# RP2040.net
KiCad netlist of a schematic drawn in Altium Designer
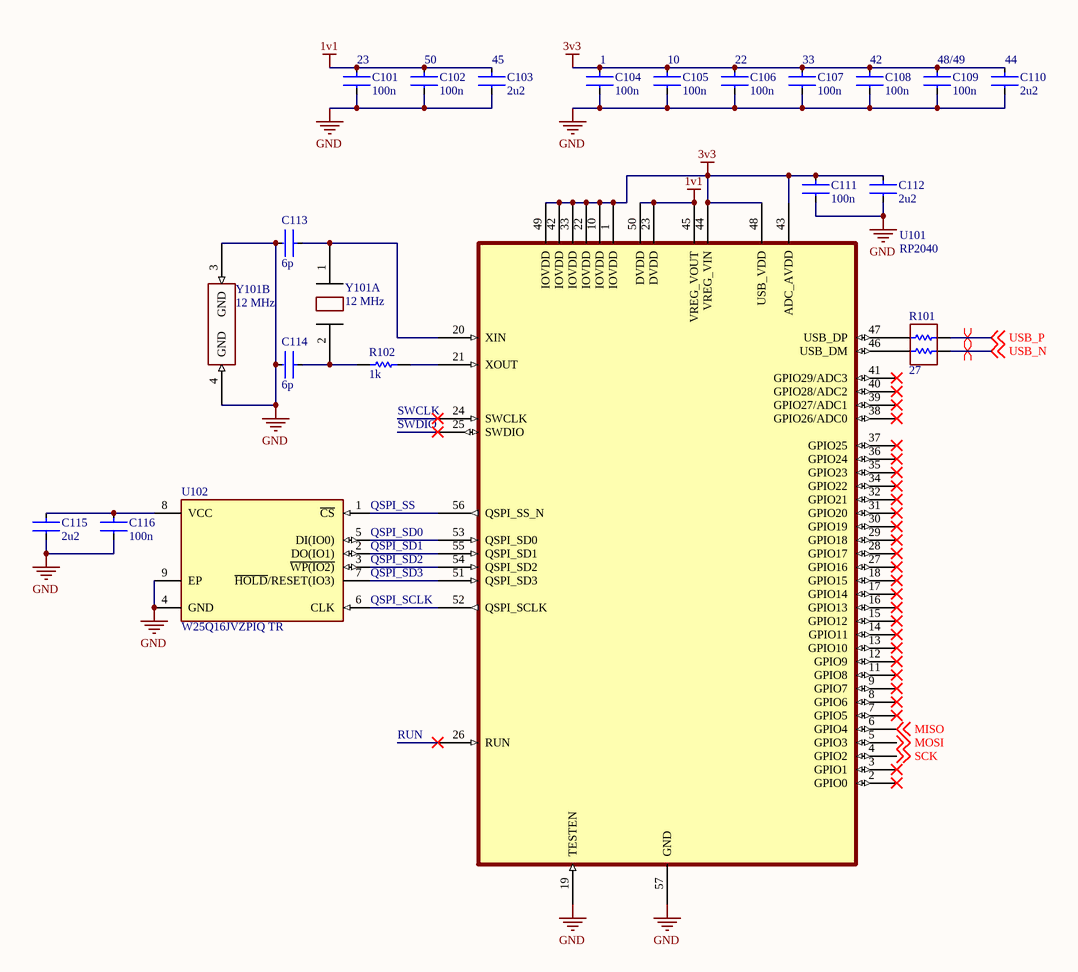
[diagram p0: RP2040.SchDoc]

(export (version "E")
  (design (tool "Eeschema 10.0.6"))
  (components
    (comp (ref "C101")
      (value "100n")
      (footprint "FP-GCM155-0_05-MFG")
      (description "Ceramic Capacitor for Automotive 100nF ±10% 50VDC X7R 0402 Paper T/R")
      (fields (field (name "TOLERANCE") "10%"))
      (libsource (lib "Main") (part "GCM155R71H104KE02J"))
    )
    (comp (ref "C102")
      (value "100n")
      (footprint "FP-GCM155-0_05-MFG")
      (description "Ceramic Capacitor for Automotive 100nF ±10% 50VDC X7R 0402 Paper T/R")
      (fields (field (name "TOLERANCE") "10%"))
      (libsource (lib "Main") (part "GCM155R71H104KE02J"))
    )
    (comp (ref "C103")
      (value "2u2")
      (footprint "CAPC1608X10N")
      (description "Multilayer Ceramic Capacitors MLCC - SMD/SMT 0603 50Vdc 2.2uF X5R 20%")
      (libsource (lib "Main") (part "GRT188R61H225ME13D"))
    )
    (comp (ref "C104")
      (value "100n")
      (footprint "FP-GCM155-0_05-MFG")
      (description "Ceramic Capacitor for Automotive 100nF ±10% 50VDC X7R 0402 Paper T/R")
      (fields (field (name "TOLERANCE") "10%"))
      (libsource (lib "Main") (part "GCM155R71H104KE02J"))
    )
    (comp (ref "C105")
      (value "100n")
      (footprint "FP-GCM155-0_05-MFG")
      (description "Ceramic Capacitor for Automotive 100nF ±10% 50VDC X7R 0402 Paper T/R")
      (fields (field (name "TOLERANCE") "10%"))
      (libsource (lib "Main") (part "GCM155R71H104KE02J"))
    )
    (comp (ref "C106")
      (value "100n")
      (footprint "FP-GCM155-0_05-MFG")
      (description "Ceramic Capacitor for Automotive 100nF ±10% 50VDC X7R 0402 Paper T/R")
      (fields (field (name "TOLERANCE") "10%"))
      (libsource (lib "Main") (part "GCM155R71H104KE02J"))
    )
    (comp (ref "C107")
      (value "100n")
      (footprint "FP-GCM155-0_05-MFG")
      (description "Ceramic Capacitor for Automotive 100nF ±10% 50VDC X7R 0402 Paper T/R")
      (fields (field (name "TOLERANCE") "10%"))
      (libsource (lib "Main") (part "GCM155R71H104KE02J"))
    )
    (comp (ref "C108")
      (value "100n")
      (footprint "FP-GCM155-0_05-MFG")
      (description "Ceramic Capacitor for Automotive 100nF ±10% 50VDC X7R 0402 Paper T/R")
      (fields (field (name "TOLERANCE") "10%"))
      (libsource (lib "Main") (part "GCM155R71H104KE02J"))
    )
    (comp (ref "C109")
      (value "100n")
      (footprint "FP-GCM155-0_05-MFG")
      (description "Ceramic Capacitor for Automotive 100nF ±10% 50VDC X7R 0402 Paper T/R")
      (fields (field (name "TOLERANCE") "10%"))
      (libsource (lib "Main") (part "GCM155R71H104KE02J"))
    )
    (comp (ref "C110")
      (value "2u2")
      (footprint "CAPC1608X10N")
      (description "Multilayer Ceramic Capacitors MLCC - SMD/SMT 0603 50Vdc 2.2uF X5R 20%")
      (libsource (lib "Main") (part "GRT188R61H225ME13D"))
    )
    (comp (ref "C111")
      (value "100n")
      (footprint "FP-GCM155-0_05-MFG")
      (description "Ceramic Capacitor for Automotive 100nF ±10% 50VDC X7R 0402 Paper T/R")
      (fields (field (name "TOLERANCE") "10%"))
      (libsource (lib "Main") (part "GCM155R71H104KE02J"))
    )
    (comp (ref "C112")
      (value "2u2")
      (footprint "CAPC1608X10N")
      (description "Multilayer Ceramic Capacitors MLCC - SMD/SMT 0603 50Vdc 2.2uF X5R 20%")
      (libsource (lib "Main") (part "GRT188R61H225ME13D"))
    )
    (comp (ref "C113")
      (value "6p")
      (footprint "FP-GCQ155-0_05-MFG")
      (description "High Q Ceramic Capacitor for Automotive 6pF ±0.1pF 50VDC C0G 0402 Paper T/R")
      (libsource (lib "Main") (part "GCQ1555C1H6R0BB01D"))
    )
    (comp (ref "C114")
      (value "6p")
      (footprint "FP-GCQ155-0_05-MFG")
      (description "High Q Ceramic Capacitor for Automotive 6pF ±0.1pF 50VDC C0G 0402 Paper T/R")
      (libsource (lib "Main") (part "GCQ1555C1H6R0BB01D"))
    )
    (comp (ref "C115")
      (value "2u2")
      (footprint "CAPC1608X10N")
      (description "Multilayer Ceramic Capacitors MLCC - SMD/SMT 0603 50Vdc 2.2uF X5R 20%")
      (libsource (lib "Main") (part "GRT188R61H225ME13D"))
    )
    (comp (ref "C116")
      (value "100n")
      (footprint "FP-GCM155-0_05-MFG")
      (description "Ceramic Capacitor for Automotive 100nF ±10% 50VDC X7R 0402 Paper T/R")
      (fields (field (name "TOLERANCE") "10%"))
      (libsource (lib "Main") (part "GCM155R71H104KE02J"))
    )
    (comp (ref "R101")
      (value "27")
      (footprint "CAC-65P100X100-4L")
      (libsource (lib "Main") (part "EXB-24V270JX"))
    )
    (comp (ref "R102")
      (value "1k")
      (footprint "RESC1005X04N")
      (fields (field (name "MANUFACTURER") "Panasonic") (field (name "PART NUMBER") "ERJ-2GEJ102X"))
      (libsource (lib "Main") (part "ERJ-2GEJ102X"))
    )
    (comp (ref "U101")
      (value "RP2040")
      (footprint "QFN40P700X700X90_HS-57N")
      (libsource (lib "Main") (part "RP2040"))
    )
    (comp (ref "U102")
      (value "W25Q16JVZPIQ TR")
      (footprint "WSON-8")
      (description "IC FLASH 16M SPI 133MHZ 8WSON")
      (libsource (lib "Main") (part "W25Q16JVZPIQ TR"))
    )
    (comp (ref "Y101") (value "12 MHz") (libsource (lib "Main") (part "ABM10-166-12.000MHZ-T3")))
  )
  (nets
    (net (code "1") (name "1v1") (class "Default")
      (node (ref "C101") (pin "1") (pinfunction "1_1") (pintype "passive"))
      (node (ref "C102") (pin "1") (pinfunction "1_1") (pintype "passive"))
      (node (ref "C103") (pin "1") (pinfunction "1_1") (pintype "passive"))
      (node (ref "U101") (pin "23") (pinfunction "DVDD_23") (pintype "power_in"))
      (node (ref "U101") (pin "45") (pinfunction "VREG_VOUT_45") (pintype "power_in"))
      (node (ref "U101") (pin "50") (pinfunction "DVDD_50") (pintype "power_in"))
    )
    (net (code "2") (name "3v3") (class "Default")
      (node (ref "C104") (pin "1") (pinfunction "1_1") (pintype "passive"))
      (node (ref "C105") (pin "1") (pinfunction "1_1") (pintype "passive"))
      (node (ref "C106") (pin "1") (pinfunction "1_1") (pintype "passive"))
      (node (ref "C107") (pin "1") (pinfunction "1_1") (pintype "passive"))
      (node (ref "C108") (pin "1") (pinfunction "1_1") (pintype "passive"))
      (node (ref "C109") (pin "1") (pinfunction "1_1") (pintype "passive"))
      (node (ref "C110") (pin "1") (pinfunction "1_1") (pintype "passive"))
      (node (ref "C111") (pin "1") (pinfunction "1_1") (pintype "passive"))
      (node (ref "C112") (pin "1") (pinfunction "1_1") (pintype "passive"))
      (node (ref "U101") (pin "1") (pinfunction "IOVDD_1") (pintype "power_in"))
      (node (ref "U101") (pin "10") (pinfunction "IOVDD_10") (pintype "power_in"))
      (node (ref "U101") (pin "22") (pinfunction "IOVDD_22") (pintype "power_in"))
      (node (ref "U101") (pin "33") (pinfunction "IOVDD_33") (pintype "power_in"))
      (node (ref "U101") (pin "42") (pinfunction "IOVDD_42") (pintype "power_in"))
      (node (ref "U101") (pin "43") (pinfunction "ADC_AVDD_43") (pintype "power_in"))
      (node (ref "U101") (pin "44") (pinfunction "VREG_VIN_44") (pintype "power_in"))
      (node (ref "U101") (pin "48") (pinfunction "USB_VDD_48") (pintype "power_in"))
      (node (ref "U101") (pin "49") (pinfunction "IOVDD_49") (pintype "power_in"))
    )
    (net (code "3") (name "GND") (class "Default")
      (node (ref "C101") (pin "2") (pinfunction "2_2") (pintype "passive"))
      (node (ref "C102") (pin "2") (pinfunction "2_2") (pintype "passive"))
      (node (ref "C103") (pin "2") (pinfunction "2_2") (pintype "passive"))
      (node (ref "C104") (pin "2") (pinfunction "2_2") (pintype "passive"))
      (node (ref "C105") (pin "2") (pinfunction "2_2") (pintype "passive"))
      (node (ref "C106") (pin "2") (pinfunction "2_2") (pintype "passive"))
      (node (ref "C107") (pin "2") (pinfunction "2_2") (pintype "passive"))
      (node (ref "C108") (pin "2") (pinfunction "2_2") (pintype "passive"))
      (node (ref "C109") (pin "2") (pinfunction "2_2") (pintype "passive"))
      (node (ref "C110") (pin "2") (pinfunction "2_2") (pintype "passive"))
      (node (ref "C111") (pin "2") (pinfunction "2_2") (pintype "passive"))
      (node (ref "C112") (pin "2") (pinfunction "2_2") (pintype "passive"))
      (node (ref "C113") (pin "2") (pinfunction "2_2") (pintype "passive"))
      (node (ref "C114") (pin "2") (pinfunction "2_2") (pintype "passive"))
      (node (ref "C115") (pin "2") (pinfunction "2_2") (pintype "passive"))
      (node (ref "C116") (pin "2") (pinfunction "2_2") (pintype "passive"))
      (node (ref "U101") (pin "19") (pinfunction "TESTEN_19") (pintype "input"))
      (node (ref "U101") (pin "57") (pinfunction "GND_57") (pintype "power_in"))
      (node (ref "U102") (pin "4") (pinfunction "GND_4") (pintype "power_in"))
      (node (ref "U102") (pin "9") (pinfunction "EP_9") (pintype "passive"))
      (node (ref "Y101") (pin "3") (pinfunction "GND_3") (pintype "input"))
      (node (ref "Y101") (pin "4") (pinfunction "GND_4") (pintype "input"))
    )
    (net (code "4") (name "MISO") (class "Default")
      (node (ref "U101") (pin "6") (pinfunction "GPIO4_6") (pintype "bidirectional"))
    )
    (net (code "5") (name "MOSI") (class "Default")
      (node (ref "U101") (pin "5") (pinfunction "GPIO3_5") (pintype "bidirectional"))
    )
    (net (code "6") (name "Net-(C114-Pad1)") (class "Default")
      (node (ref "C114") (pin "1") (pinfunction "1_1") (pintype "passive"))
      (node (ref "R102") (pin "1") (pinfunction "1_1") (pintype "passive"))
      (node (ref "Y101") (pin "2") (pintype "passive"))
    )
    (net (code "7") (name "Net-(U101-QSPI_SCLK)") (class "Default")
      (node (ref "U101") (pin "52") (pinfunction "QSPI_SCLK_52") (pintype "output"))
      (node (ref "U102") (pin "6") (pinfunction "CLK_6") (pintype "input"))
    )
    (net (code "8") (name "Net-(U101-QSPI_SD0)") (class "Default")
      (node (ref "U101") (pin "53") (pinfunction "QSPI_SD0_53") (pintype "input"))
      (node (ref "U102") (pin "5") (pinfunction "DI(IO0)_5") (pintype "bidirectional"))
    )
    (net (code "9") (name "Net-(U101-QSPI_SD1)") (class "Default")
      (node (ref "U101") (pin "55") (pinfunction "QSPI_SD1_55") (pintype "input"))
      (node (ref "U102") (pin "2") (pinfunction "DO(IO1)_2") (pintype "bidirectional"))
    )
    (net (code "10") (name "Net-(U101-QSPI_SD2)") (class "Default")
      (node (ref "U101") (pin "54") (pinfunction "QSPI_SD2_54") (pintype "input"))
      (node (ref "U102") (pin "3") (pinfunction "~{WP(IO2)}_3") (pintype "bidirectional"))
    )
    (net (code "11") (name "Net-(U101-QSPI_SD3)") (class "Default")
      (node (ref "U101") (pin "51") (pinfunction "QSPI_SD3_51") (pintype "input"))
      (node (ref "U102") (pin "7") (pinfunction "~{HOLD}/RESET(IO3)_7") (pintype "passive"))
    )
    (net (code "12") (name "Net-(U101-QSPI_SS_N)") (class "Default")
      (node (ref "U101") (pin "56") (pinfunction "QSPI_SS_N_56") (pintype "output"))
      (node (ref "U102") (pin "1") (pinfunction "~{CS}_1") (pintype "input"))
    )
    (net (code "13") (name "Net-(U101-USB_DM)") (class "Default")
      (node (ref "R101") (pin "2") (pinfunction "2_2") (pintype "passive"))
      (node (ref "U101") (pin "46") (pinfunction "USB_DM_46") (pintype "bidirectional"))
    )
    (net (code "14") (name "Net-(U101-USB_DP)") (class "Default")
      (node (ref "R101") (pin "1") (pinfunction "1_1") (pintype "passive"))
      (node (ref "U101") (pin "47") (pinfunction "USB_DP_47") (pintype "bidirectional"))
    )
    (net (code "15") (name "Net-(U101-XIN)") (class "Default")
      (node (ref "C113") (pin "1") (pinfunction "1_1") (pintype "passive"))
      (node (ref "U101") (pin "20") (pinfunction "XIN_20") (pintype "input"))
      (node (ref "Y101") (pin "1") (pintype "passive"))
    )
    (net (code "16") (name "Net-(U101-XOUT)") (class "Default")
      (node (ref "R102") (pin "2") (pinfunction "2_2") (pintype "passive"))
      (node (ref "U101") (pin "21") (pinfunction "XOUT_21") (pintype "input"))
    )
    (net (code "17") (name "Net-(U102-VCC)") (class "Default")
      (node (ref "C115") (pin "1") (pinfunction "1_1") (pintype "passive"))
      (node (ref "C116") (pin "1") (pinfunction "1_1") (pintype "passive"))
      (node (ref "U102") (pin "8") (pinfunction "VCC_8") (pintype "power_in"))
    )
    (net (code "18") (name "SCK") (class "Default")
      (node (ref "U101") (pin "4") (pinfunction "GPIO2_4") (pintype "bidirectional"))
    )
    (net (code "19") (name "USB_N") (class "Default")
      (node (ref "R101") (pin "3") (pinfunction "3_3") (pintype "passive"))
    )
    (net (code "20") (name "USB_P") (class "Default")
      (node (ref "R101") (pin "4") (pinfunction "4_4") (pintype "passive"))
    )
    (net (code "21") (name "unconnected-(U101-GPIO0-Pad2)") (class "Default")
      (node (ref "U101") (pin "2") (pinfunction "GPIO0_2") (pintype "bidirectional+no_connect"))
    )
    (net (code "22") (name "unconnected-(U101-GPIO1-Pad3)") (class "Default")
      (node (ref "U101") (pin "3") (pinfunction "GPIO1_3") (pintype "bidirectional+no_connect"))
    )
    (net (code "23") (name "unconnected-(U101-GPIO5-Pad7)") (class "Default")
      (node (ref "U101") (pin "7") (pinfunction "GPIO5_7") (pintype "bidirectional+no_connect"))
    )
    (net (code "24") (name "unconnected-(U101-GPIO6-Pad8)") (class "Default")
      (node (ref "U101") (pin "8") (pinfunction "GPIO6_8") (pintype "bidirectional+no_connect"))
    )
    (net (code "25") (name "unconnected-(U101-GPIO7-Pad9)") (class "Default")
      (node (ref "U101") (pin "9") (pinfunction "GPIO7_9") (pintype "bidirectional+no_connect"))
    )
    (net (code "26") (name "unconnected-(U101-GPIO8-Pad11)") (class "Default")
      (node (ref "U101") (pin "11") (pinfunction "GPIO8_11") (pintype "bidirectional+no_connect"))
    )
    (net (code "27") (name "unconnected-(U101-GPIO9-Pad12)") (class "Default")
      (node (ref "U101") (pin "12") (pinfunction "GPIO9_12") (pintype "bidirectional+no_connect"))
    )
    (net (code "28") (name "unconnected-(U101-GPIO10-Pad13)") (class "Default")
      (node (ref "U101") (pin "13") (pinfunction "GPIO10_13") (pintype "bidirectional+no_connect"))
    )
    (net (code "29") (name "unconnected-(U101-GPIO11-Pad14)") (class "Default")
      (node (ref "U101") (pin "14") (pinfunction "GPIO11_14") (pintype "bidirectional+no_connect"))
    )
    (net (code "30") (name "unconnected-(U101-GPIO12-Pad15)") (class "Default")
      (node (ref "U101") (pin "15") (pinfunction "GPIO12_15") (pintype "bidirectional+no_connect"))
    )
    (net (code "31") (name "unconnected-(U101-GPIO13-Pad16)") (class "Default")
      (node (ref "U101") (pin "16") (pinfunction "GPIO13_16") (pintype "bidirectional+no_connect"))
    )
    (net (code "32") (name "unconnected-(U101-GPIO14-Pad17)") (class "Default")
      (node (ref "U101") (pin "17") (pinfunction "GPIO14_17") (pintype "bidirectional+no_connect"))
    )
    (net (code "33") (name "unconnected-(U101-GPIO15-Pad18)") (class "Default")
      (node (ref "U101") (pin "18") (pinfunction "GPIO15_18") (pintype "bidirectional+no_connect"))
    )
    (net (code "34") (name "unconnected-(U101-GPIO16-Pad27)") (class "Default")
      (node (ref "U101") (pin "27") (pinfunction "GPIO16_27") (pintype "bidirectional+no_connect"))
    )
    (net (code "35") (name "unconnected-(U101-GPIO17-Pad28)") (class "Default")
      (node (ref "U101") (pin "28") (pinfunction "GPIO17_28") (pintype "bidirectional+no_connect"))
    )
    (net (code "36") (name "unconnected-(U101-GPIO18-Pad29)") (class "Default")
      (node (ref "U101") (pin "29") (pinfunction "GPIO18_29") (pintype "bidirectional+no_connect"))
    )
    (net (code "37") (name "unconnected-(U101-GPIO19-Pad30)") (class "Default")
      (node (ref "U101") (pin "30") (pinfunction "GPIO19_30") (pintype "bidirectional+no_connect"))
    )
    (net (code "38") (name "unconnected-(U101-GPIO20-Pad31)") (class "Default")
      (node (ref "U101") (pin "31") (pinfunction "GPIO20_31") (pintype "bidirectional+no_connect"))
    )
    (net (code "39") (name "unconnected-(U101-GPIO21-Pad32)") (class "Default")
      (node (ref "U101") (pin "32") (pinfunction "GPIO21_32") (pintype "bidirectional+no_connect"))
    )
    (net (code "40") (name "unconnected-(U101-GPIO22-Pad34)") (class "Default")
      (node (ref "U101") (pin "34") (pinfunction "GPIO22_34") (pintype "bidirectional+no_connect"))
    )
    (net (code "41") (name "unconnected-(U101-GPIO23-Pad35)") (class "Default")
      (node (ref "U101") (pin "35") (pinfunction "GPIO23_35") (pintype "bidirectional+no_connect"))
    )
    (net (code "42") (name "unconnected-(U101-GPIO24-Pad36)") (class "Default")
      (node (ref "U101") (pin "36") (pinfunction "GPIO24_36") (pintype "bidirectional+no_connect"))
    )
    (net (code "43") (name "unconnected-(U101-GPIO25-Pad37)") (class "Default")
      (node (ref "U101") (pin "37") (pinfunction "GPIO25_37") (pintype "bidirectional+no_connect"))
    )
    (net (code "44") (name "unconnected-(U101-GPIO26{slash}ADC0-Pad38)") (class "Default")
      (node (ref "U101") (pin "38") (pinfunction "GPIO26/ADC0_38") (pintype "bidirectional+no_connect"))
    )
    (net (code "45") (name "unconnected-(U101-GPIO27{slash}ADC1-Pad39)") (class "Default")
      (node (ref "U101") (pin "39") (pinfunction "GPIO27/ADC1_39") (pintype "bidirectional+no_connect"))
    )
    (net (code "46") (name "unconnected-(U101-GPIO28{slash}ADC2-Pad40)") (class "Default")
      (node (ref "U101") (pin "40") (pinfunction "GPIO28/ADC2_40") (pintype "bidirectional+no_connect"))
    )
    (net (code "47") (name "unconnected-(U101-GPIO29{slash}ADC3-Pad41)") (class "Default")
      (node (ref "U101") (pin "41") (pinfunction "GPIO29/ADC3_41") (pintype "bidirectional+no_connect"))
    )
    (net (code "48") (name "unconnected-(U101-RUN-Pad26)") (class "Default")
      (node (ref "U101") (pin "26") (pinfunction "RUN_26") (pintype "input+no_connect"))
    )
    (net (code "49") (name "unconnected-(U101-SWCLK-Pad24)") (class "Default")
      (node (ref "U101") (pin "24") (pinfunction "SWCLK_24") (pintype "input+no_connect"))
    )
    (net (code "50") (name "unconnected-(U101-SWDIO-Pad25)") (class "Default")
      (node (ref "U101") (pin "25") (pinfunction "SWDIO_25") (pintype "bidirectional+no_connect"))
    )
  )
)
